# MPL_Breakout.net
KiCad netlist of a schematic drawn in EAGLE
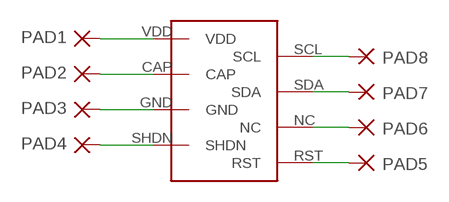
[diagram p0: schematic, sheet 1]

(export (version "E")
  (design (tool "Eeschema 10.0.6"))
  (components
    (comp (ref "B1")
      (value "MPL115A2T1")
      (footprint "eagle-import:MPL115A2T1")
      (libsource (lib "eagle-import") (part "MPL115A2T1"))
    )
    (comp (ref "PAD1")
      (value "1,6/0,8")
      (footprint "eagle-import:1,6_0,8")
      (libsource (lib "eagle-import") (part "1,6/0,8"))
    )
    (comp (ref "PAD2")
      (value "1,6/0,8")
      (footprint "eagle-import:1,6_0,8")
      (libsource (lib "eagle-import") (part "1,6/0,8"))
    )
    (comp (ref "PAD3")
      (value "1,6/0,8")
      (footprint "eagle-import:1,6_0,8")
      (libsource (lib "eagle-import") (part "1,6/0,8"))
    )
    (comp (ref "PAD4")
      (value "1,6/0,8")
      (footprint "eagle-import:1,6_0,8")
      (libsource (lib "eagle-import") (part "1,6/0,8"))
    )
    (comp (ref "PAD5")
      (value "1,6/0,8")
      (footprint "eagle-import:1,6_0,8")
      (libsource (lib "eagle-import") (part "1,6/0,8"))
    )
    (comp (ref "PAD6")
      (value "1,6/0,8")
      (footprint "eagle-import:1,6_0,8")
      (libsource (lib "eagle-import") (part "1,6/0,8"))
    )
    (comp (ref "PAD7")
      (value "1,6/0,8")
      (footprint "eagle-import:1,6_0,8")
      (libsource (lib "eagle-import") (part "1,6/0,8"))
    )
    (comp (ref "PAD8")
      (value "1,6/0,8")
      (footprint "eagle-import:1,6_0,8")
      (libsource (lib "eagle-import") (part "1,6/0,8"))
    )
  )
  (nets
    (net (code "1") (name "Net-(PAD1-P)") (class "Default")
      (node (ref "B1") (pin "VDD") (pinfunction "VDD_VDD") (pintype "bidirectional"))
      (node (ref "PAD1") (pin "1") (pinfunction "P_1") (pintype "passive"))
    )
    (net (code "2") (name "Net-(PAD2-P)") (class "Default")
      (node (ref "B1") (pin "CAP") (pinfunction "CAP_CAP") (pintype "bidirectional"))
      (node (ref "PAD2") (pin "1") (pinfunction "P_1") (pintype "passive"))
    )
    (net (code "3") (name "Net-(PAD3-P)") (class "Default")
      (node (ref "B1") (pin "GND") (pinfunction "GND_GND") (pintype "bidirectional"))
      (node (ref "PAD3") (pin "1") (pinfunction "P_1") (pintype "passive"))
    )
    (net (code "4") (name "Net-(PAD4-P)") (class "Default")
      (node (ref "B1") (pin "SHDN") (pinfunction "SHDN_SHDN") (pintype "bidirectional"))
      (node (ref "PAD4") (pin "1") (pinfunction "P_1") (pintype "passive"))
    )
    (net (code "5") (name "Net-(PAD5-P)") (class "Default")
      (node (ref "B1") (pin "RST") (pinfunction "RST_RST") (pintype "bidirectional"))
      (node (ref "PAD5") (pin "1") (pinfunction "P_1") (pintype "passive"))
    )
    (net (code "6") (name "Net-(PAD6-P)") (class "Default")
      (node (ref "B1") (pin "NC") (pinfunction "NC_NC") (pintype "bidirectional"))
      (node (ref "PAD6") (pin "1") (pinfunction "P_1") (pintype "passive"))
    )
    (net (code "7") (name "Net-(PAD7-P)") (class "Default")
      (node (ref "B1") (pin "SDA") (pinfunction "SDA_SDA") (pintype "bidirectional"))
      (node (ref "PAD7") (pin "1") (pinfunction "P_1") (pintype "passive"))
    )
    (net (code "8") (name "Net-(PAD8-P)") (class "Default")
      (node (ref "B1") (pin "SCL") (pinfunction "SCL_SCL") (pintype "bidirectional"))
      (node (ref "PAD8") (pin "1") (pinfunction "P_1") (pintype "passive"))
    )
  )
)
